# Arduino.net
KiCad netlist of a schematic drawn in Altium Designer
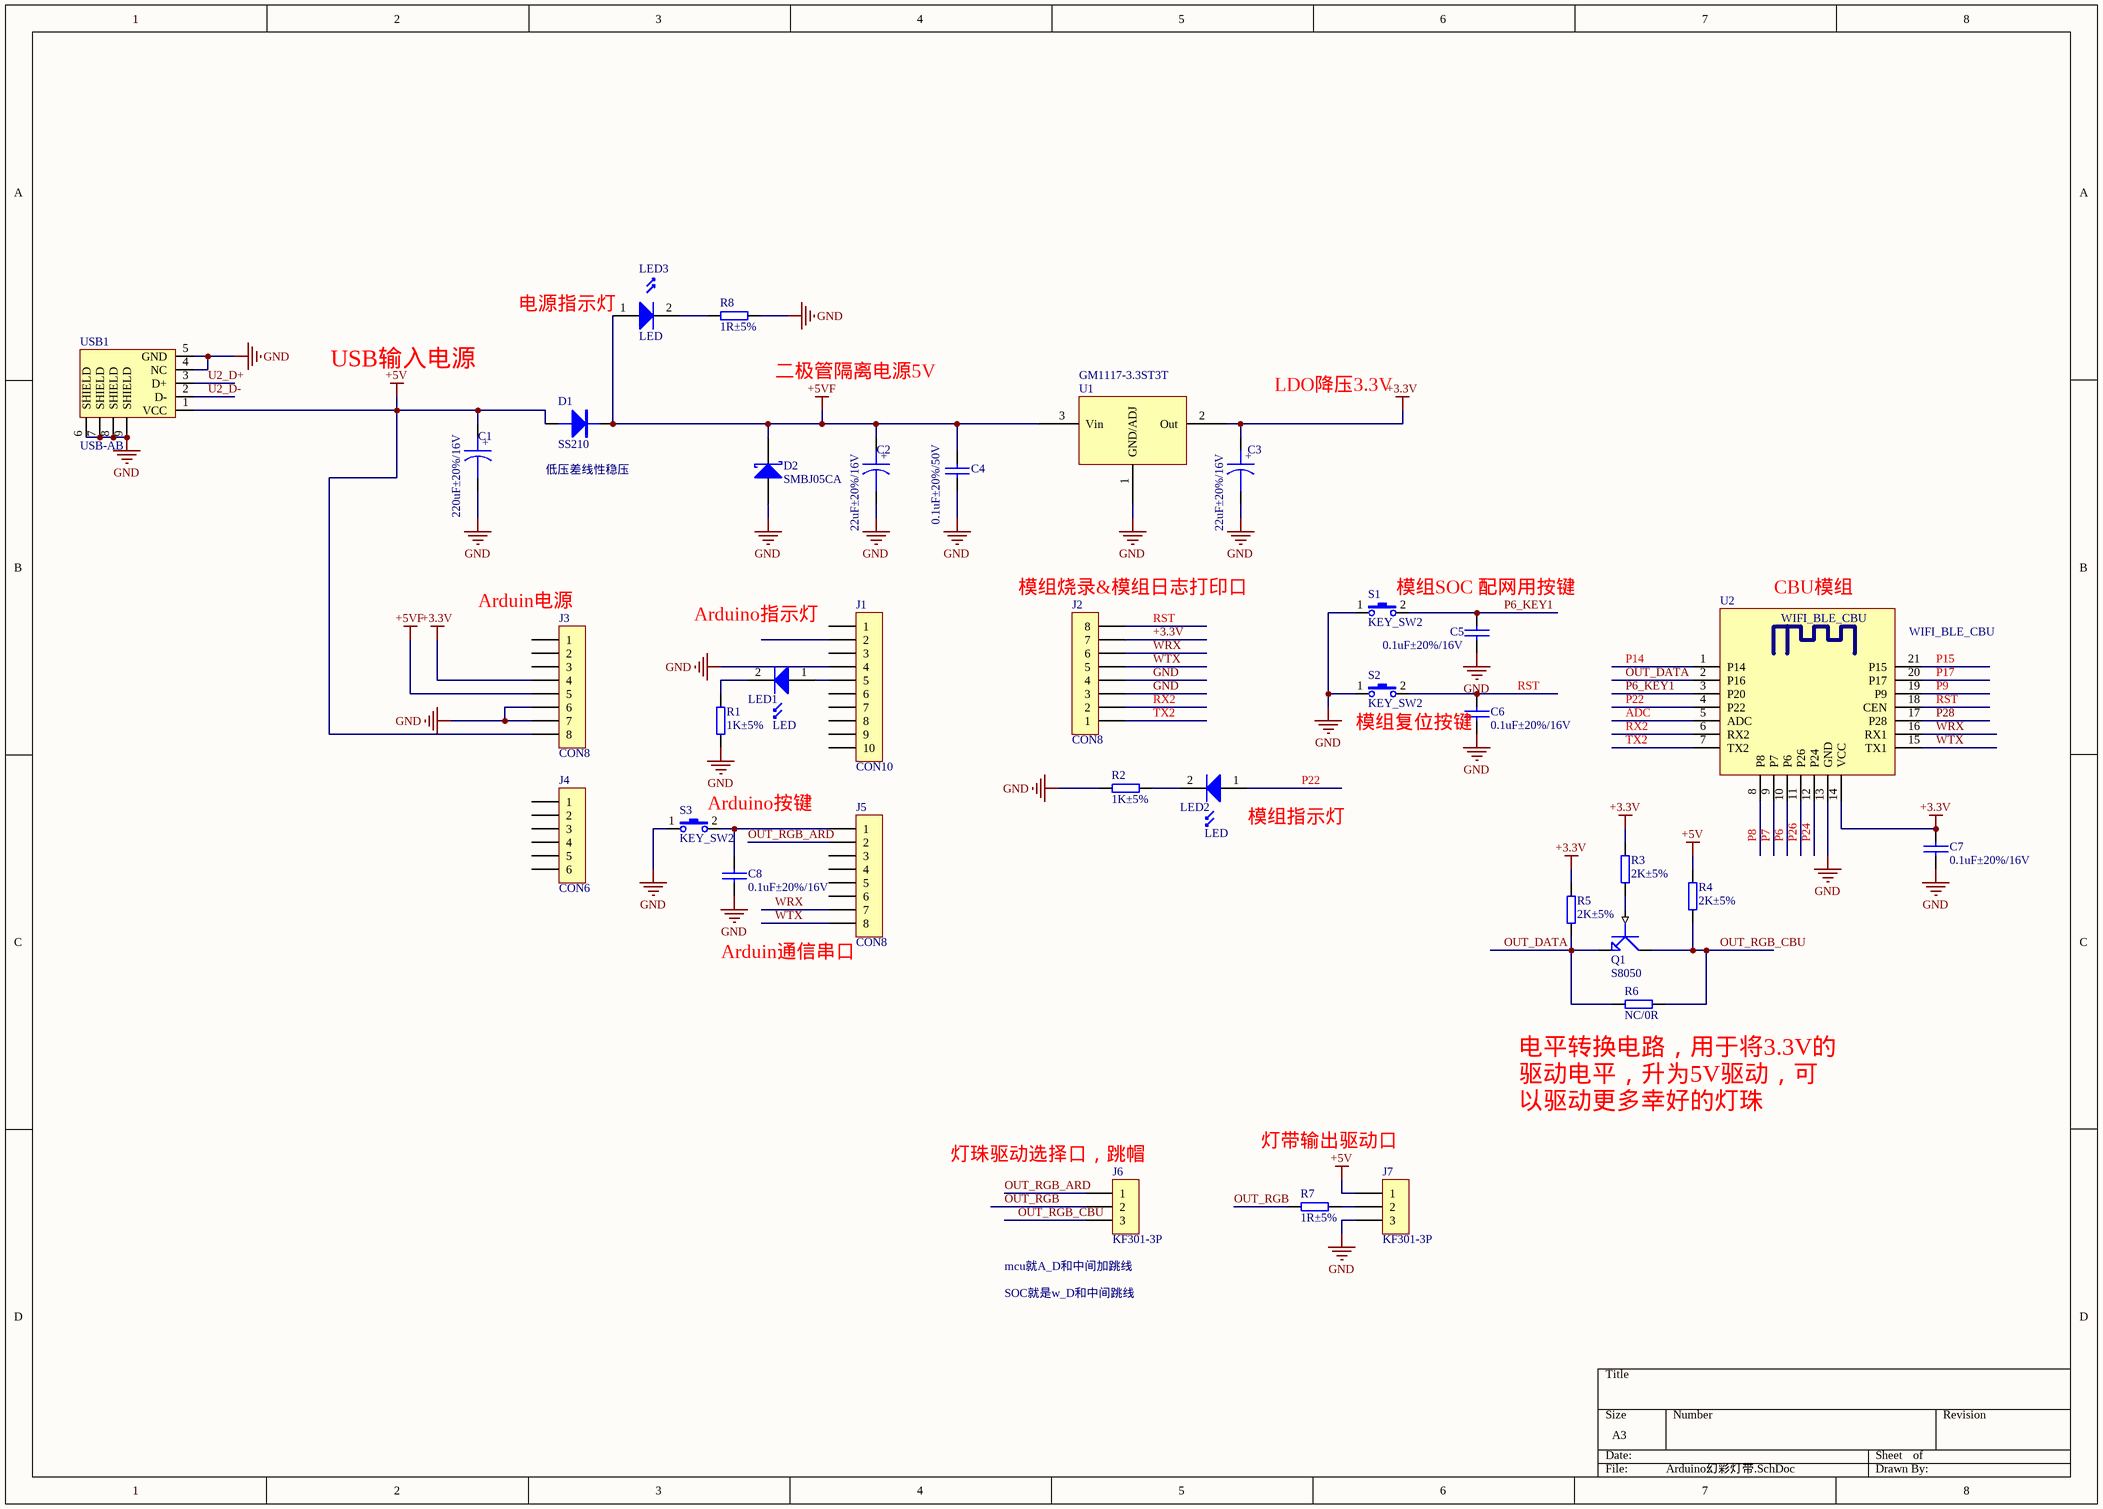
[diagram p0: Arduino幻彩灯带.SchDoc]

(export (version "E")
  (design (tool "Eeschema 10.0.6"))
  (components
    (comp (ref "C1")
      (value "220uF±20%/16V")
      (footprint "CD0.15")
      (description "Capacitor")
      (libsource (lib "*") (part "CAPACITOR POL"))
    )
    (comp (ref "C2")
      (value "22uF±20%/16V")
      (footprint "钽电容B3528")
      (description "Capacitor")
      (libsource (lib "*") (part "CAPACITOR POL"))
    )
    (comp (ref "C3")
      (value "22uF±20%/16V")
      (footprint "钽电容B3528")
      (description "Capacitor")
      (libsource (lib "*") (part "CAPACITOR POL"))
    )
    (comp (ref "C4")
      (value "0.1uF±20%/50V")
      (footprint "0805C")
      (description "Capacitor")
      (libsource (lib "昊华元件库sch") (part "CAP"))
    )
    (comp (ref "C5")
      (value "0.1uF±20%/16V")
      (footprint "0805C")
      (description "Capacitor")
      (libsource (lib "昊华元件库sch") (part "CAP"))
    )
    (comp (ref "C6")
      (value "0.1uF±20%/16V")
      (footprint "0805C")
      (description "Capacitor")
      (libsource (lib "昊华元件库sch") (part "CAP"))
    )
    (comp (ref "C7")
      (value "0.1uF±20%/16V")
      (footprint "0805C")
      (description "Capacitor")
      (libsource (lib "昊华元件库sch") (part "CAP"))
    )
    (comp (ref "C8")
      (value "0.1uF±20%/16V")
      (footprint "0805C")
      (description "Capacitor")
      (libsource (lib "昊华元件库sch") (part "CAP"))
    )
    (comp (ref "D1")
      (value "SS210")
      (footprint "SMA(DO-214AC)")
      (description "Diode")
      (libsource (lib "小马元件库sch") (part "Diode1"))
    )
    (comp (ref "D2")
      (value "SMBJ05CA")
      (footprint "SMB(DO-214AA)")
      (description "Schottky Diode")
      (fields (field (name "MFR") "Toshiba"))
      (libsource (lib "Miscellaneous Devices") (part "D Schottky"))
    )
    (comp (ref "J1")
      (value "CON10")
      (footprint "HDR1X10Z")
      (description "Connector")
      (libsource (lib "小马元件库sch") (part "CON10"))
    )
    (comp (ref "J2")
      (value "CON8")
      (footprint "HDR1X8Z")
      (description "Connector")
      (libsource (lib "") (part "CON8_1"))
    )
    (comp (ref "J3")
      (value "CON8")
      (footprint "HDR1X8Z")
      (description "Connector")
      (libsource (lib "小马元件库sch") (part "CON8"))
    )
    (comp (ref "J4")
      (value "CON6")
      (footprint "HDR1X6Z")
      (description "Connector")
      (libsource (lib "小马元件库sch") (part "CON6"))
    )
    (comp (ref "J5")
      (value "CON8")
      (footprint "HDR1X8Z")
      (description "Connector")
      (libsource (lib "小马元件库sch") (part "CON8"))
    )
    (comp (ref "J6")
      (value "KF301-3P")
      (footprint "SIP3 - 2.54")
      (description "Connector")
      (libsource (lib "小马元件库sch") (part "CON3"))
    )
    (comp (ref "J7")
      (value "KF301-3P")
      (footprint "SIP3 - 2.54")
      (description "Connector")
      (libsource (lib "小马元件库sch") (part "CON3"))
    )
    (comp (ref "LED1")
      (value "LED")
      (footprint "LED0805_1")
      (fields (field (name "PUBLISHER") "*"))
      (libsource (lib "小马元件库sch") (part "LED"))
    )
    (comp (ref "LED2")
      (value "LED")
      (footprint "LED0805_1")
      (fields (field (name "PUBLISHER") "*"))
      (libsource (lib "小马元件库sch") (part "LED"))
    )
    (comp (ref "LED3")
      (value "LED")
      (footprint "LED0805_1")
      (fields (field (name "PUBLISHER") "*"))
      (libsource (lib "小马元件库sch") (part "LED"))
    )
    (comp (ref "Q1")
      (value "S8050")
      (footprint "SOT-23-NPN")
      (description "NPN Transistor")
      (libsource (lib "小马元件库sch") (part "NPN"))
    )
    (comp (ref "R1") (value "1K±5%") (footprint "0805R") (libsource (lib "昊华元件库sch") (part "RES5")))
    (comp (ref "R2") (value "1K±5%") (footprint "0805R") (libsource (lib "昊华元件库sch") (part "RES5")))
    (comp (ref "R3") (value "2K±5%") (footprint "0805R") (libsource (lib "昊华元件库sch") (part "RES5")))
    (comp (ref "R4") (value "2K±5%") (footprint "0805R") (libsource (lib "昊华元件库sch") (part "RES5")))
    (comp (ref "R5") (value "2K±5%") (footprint "0805R") (libsource (lib "昊华元件库sch") (part "RES5")))
    (comp (ref "R6") (value "NC/0R") (footprint "0805R") (libsource (lib "昊华元件库sch") (part "RES5")))
    (comp (ref "R7") (value "1R±5%") (footprint "0805R") (libsource (lib "昊华元件库sch") (part "RES5")))
    (comp (ref "R8") (value "1R±5%") (footprint "0805R") (libsource (lib "昊华元件库sch") (part "RES5")))
    (comp (ref "S1") (value "KEY_SW2") (footprint "Button3*6") (libsource (lib "小马元件库sch") (part "KEY_SW2")))
    (comp (ref "S2") (value "KEY_SW2") (footprint "Button3*6") (libsource (lib "小马元件库sch") (part "KEY_SW2")))
    (comp (ref "S3") (value "KEY_SW2") (footprint "Button3*6") (libsource (lib "小马元件库sch") (part "KEY_SW2")))
    (comp (ref "U1") (value "GM1117-3.3ST3T") (footprint "SOT-223") (libsource (lib "mylib") (part "GM1117")))
    (comp (ref "U2")
      (value "WIFI_BLE_CBU")
      (footprint "WIFI_BLE_CBU")
      (description "Module")
      (libsource (lib "TYModeSchlib V03") (part "WIFI_BLE_CBU"))
    )
    (comp (ref "USB1")
      (value "USB-AB")
      (footprint "USB_AB_EX")
      (description "MicroUSB")
      (libsource (lib "MySchlib") (part "USB-AB"))
    )
  )
  (nets
    (net (code "1") (name "+3.3V") (class "Default")
      (node (ref "C3") (pin "1") (pinfunction "1_1") (pintype "passive"))
      (node (ref "C7") (pin "2") (pinfunction "2_2") (pintype "passive"))
      (node (ref "J2") (pin "7") (pinfunction "7_7") (pintype "passive"))
      (node (ref "J3") (pin "4") (pinfunction "4_4") (pintype "passive"))
      (node (ref "R3") (pin "1") (pinfunction "1_1") (pintype "passive"))
      (node (ref "R5") (pin "1") (pinfunction "1_1") (pintype "passive"))
      (node (ref "U1") (pin "2") (pinfunction "Out_2") (pintype "passive"))
      (node (ref "U2") (pin "14") (pinfunction "VCC_14") (pintype "passive"))
    )
    (net (code "2") (name "+5V") (class "Default")
      (node (ref "C1") (pin "1") (pinfunction "1_1") (pintype "passive"))
      (node (ref "D1") (pin "1") (pinfunction "1_1") (pintype "passive"))
      (node (ref "J3") (pin "8") (pinfunction "8_8") (pintype "passive"))
      (node (ref "J7") (pin "1") (pinfunction "1_1") (pintype "passive"))
      (node (ref "R4") (pin "1") (pinfunction "1_1") (pintype "passive"))
      (node (ref "USB1") (pin "1") (pinfunction "VCC_1") (pintype "passive"))
    )
    (net (code "3") (name "+5VF") (class "Default")
      (node (ref "C2") (pin "1") (pinfunction "1_1") (pintype "passive"))
      (node (ref "C4") (pin "1") (pinfunction "1_1") (pintype "passive"))
      (node (ref "D1") (pin "2") (pinfunction "2_2") (pintype "passive"))
      (node (ref "D2") (pin "2") (pinfunction "K_2") (pintype "passive"))
      (node (ref "J3") (pin "5") (pinfunction "5_5") (pintype "passive"))
      (node (ref "LED3") (pin "1") (pinfunction "1_1") (pintype "passive"))
      (node (ref "U1") (pin "3") (pinfunction "Vin_3") (pintype "passive"))
    )
    (net (code "4") (name "/ADC") (class "Default")
      (node (ref "U2") (pin "5") (pinfunction "ADC_5") (pintype "passive"))
    )
    (net (code "5") (name "/OUT_DATA") (class "Default")
      (node (ref "Q1") (pin "1") (pinfunction "E_1") (pintype "passive"))
      (node (ref "R5") (pin "2") (pinfunction "2_2") (pintype "passive"))
      (node (ref "R6") (pin "1") (pinfunction "1_1") (pintype "passive"))
      (node (ref "U2") (pin "2") (pinfunction "P16_2") (pintype "passive"))
    )
    (net (code "6") (name "/OUT_RGB") (class "Default")
      (node (ref "J6") (pin "2") (pinfunction "2_2") (pintype "passive"))
      (node (ref "R7") (pin "1") (pinfunction "1_1") (pintype "passive"))
    )
    (net (code "7") (name "/OUT_RGB_ARD") (class "Default")
      (node (ref "J5") (pin "2") (pinfunction "2_2") (pintype "passive"))
      (node (ref "J6") (pin "1") (pinfunction "1_1") (pintype "passive"))
    )
    (net (code "8") (name "/OUT_RGB_CBU") (class "Default")
      (node (ref "J6") (pin "3") (pinfunction "3_3") (pintype "passive"))
      (node (ref "Q1") (pin "3") (pinfunction "C_3") (pintype "passive"))
      (node (ref "R4") (pin "2") (pinfunction "2_2") (pintype "passive"))
      (node (ref "R6") (pin "2") (pinfunction "2_2") (pintype "passive"))
    )
    (net (code "9") (name "/P6") (class "Default")
      (node (ref "U2") (pin "10") (pinfunction "P6_10") (pintype "passive"))
    )
    (net (code "10") (name "/P6_KEY1") (class "Default")
      (node (ref "C5") (pin "2") (pinfunction "2_2") (pintype "passive"))
      (node (ref "S1") (pin "2") (pinfunction "2_2") (pintype "passive"))
      (node (ref "U2") (pin "3") (pinfunction "P20_3") (pintype "passive"))
    )
    (net (code "11") (name "/P7") (class "Default")
      (node (ref "U2") (pin "9") (pinfunction "P7_9") (pintype "passive"))
    )
    (net (code "12") (name "/P8") (class "Default")
      (node (ref "U2") (pin "8") (pinfunction "P8_8") (pintype "passive"))
    )
    (net (code "13") (name "/P9") (class "Default")
      (node (ref "U2") (pin "19") (pinfunction "P9_19") (pintype "passive"))
    )
    (net (code "14") (name "/P14") (class "Default")
      (node (ref "U2") (pin "1") (pinfunction "P14_1") (pintype "passive"))
    )
    (net (code "15") (name "/P15") (class "Default")
      (node (ref "U2") (pin "21") (pinfunction "P15_21") (pintype "passive"))
    )
    (net (code "16") (name "/P17") (class "Default")
      (node (ref "U2") (pin "20") (pinfunction "P17_20") (pintype "passive"))
    )
    (net (code "17") (name "/P22") (class "Default")
      (node (ref "LED2") (pin "1") (pinfunction "1_1") (pintype "passive"))
      (node (ref "U2") (pin "4") (pinfunction "P22_4") (pintype "passive"))
    )
    (net (code "18") (name "/P24") (class "Default")
      (node (ref "U2") (pin "12") (pinfunction "P24_12") (pintype "passive"))
    )
    (net (code "19") (name "/P26") (class "Default")
      (node (ref "U2") (pin "11") (pinfunction "P26_11") (pintype "passive"))
    )
    (net (code "20") (name "/P28") (class "Default")
      (node (ref "U2") (pin "17") (pinfunction "P28_17") (pintype "passive"))
    )
    (net (code "21") (name "/RST") (class "Default")
      (node (ref "C6") (pin "1") (pinfunction "1_1") (pintype "passive"))
      (node (ref "J2") (pin "8") (pinfunction "8_8") (pintype "passive"))
      (node (ref "S2") (pin "2") (pinfunction "2_2") (pintype "passive"))
      (node (ref "U2") (pin "18") (pinfunction "CEN_18") (pintype "passive"))
    )
    (net (code "22") (name "/RX2") (class "Default")
      (node (ref "J2") (pin "2") (pinfunction "2_2") (pintype "passive"))
      (node (ref "U2") (pin "6") (pinfunction "RX2_6") (pintype "passive"))
    )
    (net (code "23") (name "/TX2") (class "Default")
      (node (ref "J2") (pin "1") (pinfunction "1_1") (pintype "passive"))
      (node (ref "U2") (pin "7") (pinfunction "TX2_7") (pintype "passive"))
    )
    (net (code "24") (name "/U2_D+") (class "Default")
      (node (ref "USB1") (pin "3") (pinfunction "D+_3") (pintype "passive"))
    )
    (net (code "25") (name "/U2_D-") (class "Default")
      (node (ref "USB1") (pin "2") (pinfunction "D-_2") (pintype "passive"))
    )
    (net (code "26") (name "/WRX") (class "Default")
      (node (ref "J2") (pin "6") (pinfunction "6_6") (pintype "passive"))
      (node (ref "J5") (pin "7") (pinfunction "7_7") (pintype "passive"))
      (node (ref "U2") (pin "16") (pinfunction "RX1_16") (pintype "passive"))
    )
    (net (code "27") (name "/WTX") (class "Default")
      (node (ref "J2") (pin "5") (pinfunction "5_5") (pintype "passive"))
      (node (ref "J5") (pin "8") (pinfunction "8_8") (pintype "passive"))
      (node (ref "U2") (pin "15") (pinfunction "TX1_15") (pintype "passive"))
    )
    (net (code "28") (name "GND") (class "Default")
      (node (ref "C1") (pin "2") (pinfunction "2_2") (pintype "passive"))
      (node (ref "C2") (pin "2") (pinfunction "2_2") (pintype "passive"))
      (node (ref "C3") (pin "2") (pinfunction "2_2") (pintype "passive"))
      (node (ref "C4") (pin "2") (pinfunction "2_2") (pintype "passive"))
      (node (ref "C5") (pin "1") (pinfunction "1_1") (pintype "passive"))
      (node (ref "C6") (pin "2") (pinfunction "2_2") (pintype "passive"))
      (node (ref "C7") (pin "1") (pinfunction "1_1") (pintype "passive"))
      (node (ref "C8") (pin "1") (pinfunction "1_1") (pintype "passive"))
      (node (ref "D2") (pin "1") (pinfunction "A_1") (pintype "passive"))
      (node (ref "J1") (pin "4") (pinfunction "4_4") (pintype "passive"))
      (node (ref "J2") (pin "3") (pinfunction "3_3") (pintype "passive"))
      (node (ref "J2") (pin "4") (pinfunction "4_4") (pintype "passive"))
      (node (ref "J3") (pin "6") (pinfunction "6_6") (pintype "passive"))
      (node (ref "J3") (pin "7") (pinfunction "7_7") (pintype "passive"))
      (node (ref "J7") (pin "3") (pinfunction "3_3") (pintype "passive"))
      (node (ref "R1") (pin "1") (pinfunction "1_1") (pintype "passive"))
      (node (ref "R2") (pin "2") (pinfunction "2_2") (pintype "passive"))
      (node (ref "R8") (pin "2") (pinfunction "2_2") (pintype "passive"))
      (node (ref "S1") (pin "1") (pinfunction "1_1") (pintype "passive"))
      (node (ref "S2") (pin "1") (pinfunction "1_1") (pintype "passive"))
      (node (ref "S3") (pin "1") (pinfunction "1_1") (pintype "passive"))
      (node (ref "U1") (pin "1") (pinfunction "GND/ADJ_1") (pintype "passive"))
      (node (ref "U2") (pin "13") (pinfunction "GND_13") (pintype "passive"))
      (node (ref "USB1") (pin "4") (pinfunction "NC_4") (pintype "passive"))
      (node (ref "USB1") (pin "5") (pinfunction "GND_5") (pintype "passive"))
      (node (ref "USB1") (pin "6") (pinfunction "SHIELD_6") (pintype "passive"))
      (node (ref "USB1") (pin "7") (pinfunction "SHIELD_7") (pintype "passive"))
      (node (ref "USB1") (pin "8") (pinfunction "SHIELD_8") (pintype "passive"))
      (node (ref "USB1") (pin "9") (pinfunction "SHIELD_9") (pintype "passive"))
    )
    (net (code "29") (name "Net-(C8-Pad2)") (class "Default")
      (node (ref "C8") (pin "2") (pinfunction "2_2") (pintype "passive"))
      (node (ref "J5") (pin "1") (pinfunction "1_1") (pintype "passive"))
      (node (ref "S3") (pin "2") (pinfunction "2_2") (pintype "passive"))
    )
    (net (code "30") (name "Net-(J1-Pad5)") (class "Default")
      (node (ref "J1") (pin "5") (pinfunction "5_5") (pintype "passive"))
      (node (ref "LED1") (pin "1") (pinfunction "1_1") (pintype "passive"))
    )
    (net (code "31") (name "Net-(J7-Pad2)") (class "Default")
      (node (ref "J7") (pin "2") (pinfunction "2_2") (pintype "passive"))
      (node (ref "R7") (pin "2") (pinfunction "2_2") (pintype "passive"))
    )
    (net (code "32") (name "Net-(LED1-Pad2)") (class "Default")
      (node (ref "LED1") (pin "2") (pinfunction "2_2") (pintype "passive"))
      (node (ref "R1") (pin "2") (pinfunction "2_2") (pintype "passive"))
    )
    (net (code "33") (name "Net-(LED2-Pad2)") (class "Default")
      (node (ref "LED2") (pin "2") (pinfunction "2_2") (pintype "passive"))
      (node (ref "R2") (pin "1") (pinfunction "1_1") (pintype "passive"))
    )
    (net (code "34") (name "Net-(LED3-Pad2)") (class "Default")
      (node (ref "LED3") (pin "2") (pinfunction "2_2") (pintype "passive"))
      (node (ref "R8") (pin "1") (pinfunction "1_1") (pintype "passive"))
    )
    (net (code "35") (name "Net-(Q1-B)") (class "Default")
      (node (ref "Q1") (pin "2") (pinfunction "B_2") (pintype "input"))
      (node (ref "R3") (pin "2") (pinfunction "2_2") (pintype "passive"))
    )
    (net (code "36") (name "unconnected-(J1-Pad1)") (class "Default")
      (node (ref "J1") (pin "1") (pinfunction "1_1") (pintype "passive"))
    )
    (net (code "37") (name "unconnected-(J1-Pad2)") (class "Default")
      (node (ref "J1") (pin "2") (pinfunction "2_2") (pintype "passive"))
    )
    (net (code "38") (name "unconnected-(J1-Pad3)") (class "Default")
      (node (ref "J1") (pin "3") (pinfunction "3_3") (pintype "passive"))
    )
    (net (code "39") (name "unconnected-(J1-Pad6)") (class "Default")
      (node (ref "J1") (pin "6") (pinfunction "6_6") (pintype "passive"))
    )
    (net (code "40") (name "unconnected-(J1-Pad7)") (class "Default")
      (node (ref "J1") (pin "7") (pinfunction "7_7") (pintype "passive"))
    )
    (net (code "41") (name "unconnected-(J1-Pad8)") (class "Default")
      (node (ref "J1") (pin "8") (pinfunction "8_8") (pintype "passive"))
    )
    (net (code "42") (name "unconnected-(J1-Pad9)") (class "Default")
      (node (ref "J1") (pin "9") (pinfunction "9_9") (pintype "passive"))
    )
    (net (code "43") (name "unconnected-(J1-Pad10)") (class "Default")
      (node (ref "J1") (pin "10") (pinfunction "10_10") (pintype "passive"))
    )
    (net (code "44") (name "unconnected-(J3-Pad1)") (class "Default")
      (node (ref "J3") (pin "1") (pinfunction "1_1") (pintype "passive"))
    )
    (net (code "45") (name "unconnected-(J3-Pad2)") (class "Default")
      (node (ref "J3") (pin "2") (pinfunction "2_2") (pintype "passive"))
    )
    (net (code "46") (name "unconnected-(J3-Pad3)") (class "Default")
      (node (ref "J3") (pin "3") (pinfunction "3_3") (pintype "passive"))
    )
    (net (code "47") (name "unconnected-(J4-Pad1)") (class "Default")
      (node (ref "J4") (pin "1") (pinfunction "1_1") (pintype "passive"))
    )
    (net (code "48") (name "unconnected-(J4-Pad2)") (class "Default")
      (node (ref "J4") (pin "2") (pinfunction "2_2") (pintype "passive"))
    )
    (net (code "49") (name "unconnected-(J4-Pad3)") (class "Default")
      (node (ref "J4") (pin "3") (pinfunction "3_3") (pintype "passive"))
    )
    (net (code "50") (name "unconnected-(J4-Pad4)") (class "Default")
      (node (ref "J4") (pin "4") (pinfunction "4_4") (pintype "passive"))
    )
    (net (code "51") (name "unconnected-(J4-Pad5)") (class "Default")
      (node (ref "J4") (pin "5") (pinfunction "5_5") (pintype "passive"))
    )
    (net (code "52") (name "unconnected-(J4-Pad6)") (class "Default")
      (node (ref "J4") (pin "6") (pinfunction "6_6") (pintype "passive"))
    )
    (net (code "53") (name "unconnected-(J5-Pad3)") (class "Default")
      (node (ref "J5") (pin "3") (pinfunction "3_3") (pintype "passive"))
    )
    (net (code "54") (name "unconnected-(J5-Pad4)") (class "Default")
      (node (ref "J5") (pin "4") (pinfunction "4_4") (pintype "passive"))
    )
    (net (code "55") (name "unconnected-(J5-Pad5)") (class "Default")
      (node (ref "J5") (pin "5") (pinfunction "5_5") (pintype "passive"))
    )
    (net (code "56") (name "unconnected-(J5-Pad6)") (class "Default")
      (node (ref "J5") (pin "6") (pinfunction "6_6") (pintype "passive"))
    )
  )
)
